# design.net
KiCad netlist of a schematic drawn in Altium Designer
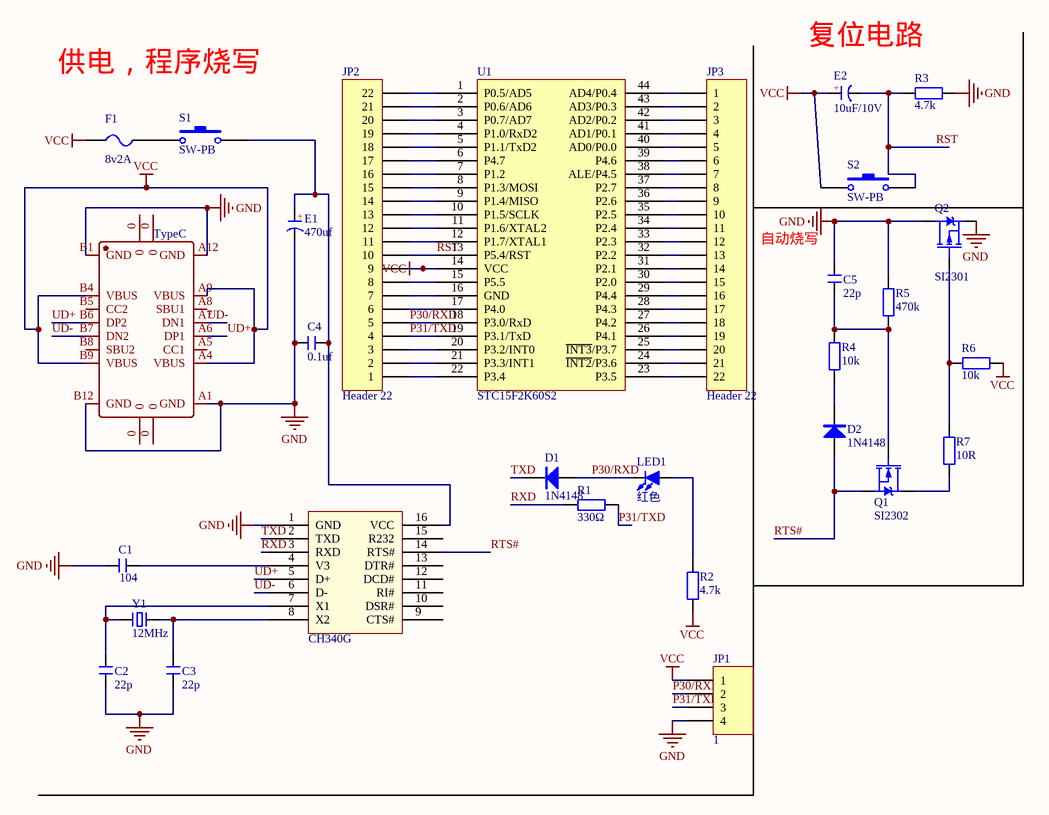
[diagram p0: 小车.SchDoc]

(export (version "E")
  (design (tool "Eeschema 10.0.6"))
  (components
    (comp (ref "C1")
      (value "104")
      (footprint "C 0805")
      (description "无极性贴片电容")
      (fields (field (name "版权归属") "黎明电子style"))
      (libsource (lib "基地硬件部AD库3.01") (part "C"))
    )
    (comp (ref "C2")
      (value "22p")
      (footprint "C 0805")
      (description "无极性贴片电容")
      (fields (field (name "版权归属") "黎明电子style"))
      (libsource (lib "基地硬件部AD库3.01") (part "C"))
    )
    (comp (ref "C3")
      (value "22p")
      (footprint "C 0805")
      (description "无极性贴片电容")
      (fields (field (name "版权归属") "黎明电子style"))
      (libsource (lib "基地硬件部AD库3.01") (part "C"))
    )
    (comp (ref "C4")
      (value "0.1uf")
      (footprint "C 0805")
      (description "无极性贴片电容")
      (fields (field (name "版权归属") "黎明电子style"))
      (libsource (lib "基地硬件部AD库3.01") (part "C"))
    )
    (comp (ref "C5")
      (value "22p")
      (footprint "C 0805")
      (description "无极性贴片电容")
      (fields (field (name "版权归属") "黎明电子style"))
      (libsource (lib "基地硬件部AD库3.01") (part "C"))
    )
    (comp (ref "CH340G") (value "CH340G") (footprint "sop16_L") (libsource (lib "主集成库") (part "CH340G")))
    (comp (ref "D1")
      (value "1N4148")
      (footprint "MINI_MELF (LL34)")
      (description "高速开关二极管")
      (fields (field (name "版权归属") "源创客"))
      (libsource (lib "基地硬件部AD库3.01") (part "1N4148"))
    )
    (comp (ref "D2")
      (value "1N4148")
      (footprint "MINI_MELF (LL34)")
      (description "高速开关二极管")
      (fields (field (name "版权归属") "源创客"))
      (libsource (lib "基地硬件部AD库3.01") (part "1N4148"))
    )
    (comp (ref "E1")
      (value "470uf")
      (footprint "CM A(3*5.4)")
      (description "贴片电解电容")
      (fields (field (name "版权归属") "黎明电子style"))
      (libsource (lib "") (part "C-CM_1"))
    )
    (comp (ref "E2")
      (value "10uF/10V")
      (footprint "CM A(3*5.4)")
      (description "贴片电解电容")
      (fields (field (name "版权归属") "黎明电子style"))
      (libsource (lib "基地硬件部AD库3.01") (part "C-CM"))
    )
    (comp (ref "F1")
      (value "8v2A")
      (footprint "FU 0402")
      (description "贴片保险丝")
      (fields (field (name "版权归属") "源创客"))
      (libsource (lib "基地硬件部AD库3.01") (part "FU"))
    )
    (comp (ref "JP1")
      (value "1")
      (footprint "HDR1X4")
      (description "Header, 4-Pin")
      (fields (field (name "PUBLISHER") "Altium Limited"))
      (libsource (lib "Miscellaneous Connectors") (part "Header 4"))
    )
    (comp (ref "JP2")
      (value "Header 22")
      (footprint "HDR1X22")
      (description "Header, 22-Pin")
      (fields (field (name "PUBLISHER") "Altium Limited"))
      (libsource (lib "Miscellaneous Connectors") (part "Header 22"))
    )
    (comp (ref "JP3")
      (value "Header 22")
      (footprint "HDR1X22")
      (description "Header, 22-Pin")
      (fields (field (name "PUBLISHER") "Altium Limited"))
      (libsource (lib "") (part "Header 22_1"))
    )
    (comp (ref "LED1")
      (value "红色")
      (footprint "LED 0805G")
      (description "贴片LED")
      (fields (field (name "版权归属") "黎明电子style"))
      (libsource (lib "基地硬件部AD库3.01") (part "LED-SMD"))
    )
    (comp (ref "Q1")
      (value "SI2302")
      (footprint "SOT23-3N")
      (description "N沟道场效应管")
      (fields (field (name "版权归属") "黎明电子style"))
      (libsource (lib "基地硬件部AD库3.01") (part "SI2302"))
    )
    (comp (ref "Q2")
      (value "SI2301")
      (footprint "SOT23-3N")
      (description "P沟道场效应管")
      (fields (field (name "版权归属") "黎明电子style"))
      (libsource (lib "基地硬件部AD库3.01") (part "SI2301"))
    )
    (comp (ref "R1")
      (value "330Ω")
      (footprint "R 0805")
      (description "贴片电阻")
      (fields (field (name "版权归属") "黎明电子style"))
      (libsource (lib "基地硬件部AD库3.01") (part "R"))
    )
    (comp (ref "R2")
      (value "4.7k")
      (footprint "R 0805")
      (description "贴片电阻")
      (fields (field (name "版权归属") "黎明电子style"))
      (libsource (lib "基地硬件部AD库3.01") (part "R"))
    )
    (comp (ref "R3")
      (value "4.7k")
      (footprint "R 0805")
      (description "贴片电阻")
      (fields (field (name "版权归属") "黎明电子style"))
      (libsource (lib "基地硬件部AD库3.01") (part "R"))
    )
    (comp (ref "R4")
      (value "10k")
      (footprint "R 0805")
      (description "贴片电阻")
      (fields (field (name "版权归属") "黎明电子style"))
      (libsource (lib "基地硬件部AD库3.01") (part "R"))
    )
    (comp (ref "R5")
      (value "470k")
      (footprint "R 0805")
      (description "贴片电阻")
      (fields (field (name "版权归属") "黎明电子style"))
      (libsource (lib "基地硬件部AD库3.01") (part "R"))
    )
    (comp (ref "R6")
      (value "10k")
      (footprint "R 0805")
      (description "贴片电阻")
      (fields (field (name "版权归属") "黎明电子style"))
      (libsource (lib "基地硬件部AD库3.01") (part "R"))
    )
    (comp (ref "R7")
      (value "10R")
      (footprint "R 0805")
      (description "贴片电阻")
      (fields (field (name "版权归属") "黎明电子style"))
      (libsource (lib "基地硬件部AD库3.01") (part "R"))
    )
    (comp (ref "S1")
      (value "SW-PB")
      (footprint "SW_PB2_A1")
      (description "微动开关")
      (fields (field (name "PUBLISHER") "Altium Limited"))
      (libsource (lib "主集成库") (part "SW-PB"))
    )
    (comp (ref "S2")
      (value "SW-PB")
      (footprint "SW_PB2_A1")
      (description "微动开关")
      (fields (field (name "PUBLISHER") "Altium Limited"))
      (libsource (lib "主集成库") (part "SW-PB"))
    )
    (comp (ref "TypeC")
      (value "TypeC-16pin")
      (footprint "typeC-16pin")
      (description "USB-C-16Pin")
      (libsource (lib "基地硬件部AD库3.01") (part "TypeC-16pin"))
    )
    (comp (ref "U1")
      (value "STC15F2K60S2")
      (footprint "LQFP44 10X10_L")
      (description "STC单片机")
      (fields (field (name "版权归属") "校基地硬件部"))
      (libsource (lib "基地硬件部AD库3.01") (part "STC15F2K60S2-44pin"))
    )
    (comp (ref "Y1")
      (value "12MHz")
      (footprint "OSC HC-49SMD")
      (description "2脚无源脚晶振")
      (fields (field (name "版权归属") "源创客"))
      (libsource (lib "基地硬件部AD库3.01") (part "XTAL-2P"))
    )
  )
  (nets
    (net (code "1") (name "/P30{slash}RXD") (class "Default")
      (node (ref "D1") (pin "1") (pinfunction "A_1") (pintype "passive"))
      (node (ref "JP1") (pin "2") (pinfunction "2_2") (pintype "passive"))
      (node (ref "JP2") (pin "5") (pinfunction "5_5") (pintype "passive"))
      (node (ref "LED1") (pin "2") (pinfunction "K_2") (pintype "passive"))
      (node (ref "U1") (pin "18") (pinfunction "P3.0/RxD_18") (pintype "passive"))
    )
    (net (code "2") (name "/P31{slash}TXD") (class "Default")
      (node (ref "JP1") (pin "3") (pinfunction "3_3") (pintype "passive"))
      (node (ref "JP2") (pin "4") (pinfunction "4_4") (pintype "passive"))
      (node (ref "R1") (pin "2") (pinfunction "2_2") (pintype "passive"))
      (node (ref "U1") (pin "19") (pinfunction "P3.1/TxD_19") (pintype "passive"))
    )
    (net (code "3") (name "/RST") (class "Default")
      (node (ref "E2") (pin "2") (pinfunction "K_2") (pintype "passive"))
      (node (ref "JP2") (pin "10") (pinfunction "10_10") (pintype "passive"))
      (node (ref "R3") (pin "2") (pinfunction "2_2") (pintype "passive"))
      (node (ref "S2") (pin "2") (pinfunction "2_2") (pintype "passive"))
      (node (ref "U1") (pin "13") (pinfunction "P5.4/RST_13") (pintype "passive"))
    )
    (net (code "4") (name "/RTS#") (class "Default")
      (node (ref "CH340G") (pin "14") (pinfunction "RTS#_14") (pintype "passive"))
      (node (ref "D2") (pin "1") (pinfunction "A_1") (pintype "passive"))
      (node (ref "Q1") (pin "2") (pinfunction "S_2") (pintype "passive"))
    )
    (net (code "5") (name "/RXD") (class "Default")
      (node (ref "CH340G") (pin "3") (pinfunction "RXD_3") (pintype "passive"))
      (node (ref "R1") (pin "1") (pinfunction "1_1") (pintype "passive"))
    )
    (net (code "6") (name "/TXD") (class "Default")
      (node (ref "CH340G") (pin "2") (pinfunction "TXD_2") (pintype "passive"))
      (node (ref "D1") (pin "2") (pinfunction "K_2") (pintype "passive"))
    )
    (net (code "7") (name "/UD+") (class "Default")
      (node (ref "CH340G") (pin "5") (pinfunction "D+_5") (pintype "passive"))
      (node (ref "TypeC") (pin "A6") (pinfunction "DP1_A6") (pintype "passive"))
      (node (ref "TypeC") (pin "B6") (pinfunction "DP2_B6") (pintype "passive"))
    )
    (net (code "8") (name "/UD-") (class "Default")
      (node (ref "CH340G") (pin "6") (pinfunction "D-_6") (pintype "passive"))
      (node (ref "TypeC") (pin "A7") (pinfunction "DN1_A7") (pintype "passive"))
      (node (ref "TypeC") (pin "B7") (pinfunction "DN2_B7") (pintype "passive"))
    )
    (net (code "9") (name "GND") (class "Default")
      (node (ref "C1") (pin "1") (pinfunction "1_1") (pintype "passive"))
      (node (ref "C2") (pin "2") (pinfunction "2_2") (pintype "passive"))
      (node (ref "C3") (pin "2") (pinfunction "2_2") (pintype "passive"))
      (node (ref "C4") (pin "1") (pinfunction "1_1") (pintype "passive"))
      (node (ref "C5") (pin "1") (pinfunction "1_1") (pintype "passive"))
      (node (ref "CH340G") (pin "1") (pinfunction "GND_1") (pintype "passive"))
      (node (ref "E1") (pin "2") (pinfunction "K_2") (pintype "passive"))
      (node (ref "JP1") (pin "4") (pinfunction "4_4") (pintype "passive"))
      (node (ref "Q2") (pin "2") (pinfunction "S_2") (pintype "passive"))
      (node (ref "Q2") (pin "3") (pinfunction "D_3") (pintype "passive"))
      (node (ref "R3") (pin "1") (pinfunction "1_1") (pintype "passive"))
      (node (ref "R5") (pin "1") (pinfunction "1_1") (pintype "passive"))
      (node (ref "TypeC") (pin "A1") (pinfunction "GND_A1") (pintype "passive"))
      (node (ref "TypeC") (pin "A12") (pinfunction "GND_A12") (pintype "passive"))
      (node (ref "TypeC") (pin "B1") (pinfunction "GND_B1") (pintype "passive"))
      (node (ref "TypeC") (pin "B12") (pinfunction "GND_B12") (pintype "passive"))
    )
    (net (code "10") (name "Net-(CH340G-V3)") (class "Default")
      (node (ref "C1") (pin "2") (pinfunction "2_2") (pintype "passive"))
      (node (ref "CH340G") (pin "4") (pinfunction "V3_4") (pintype "passive"))
    )
    (net (code "11") (name "Net-(CH340G-VCC)") (class "Default")
      (node (ref "C4") (pin "2") (pinfunction "2_2") (pintype "passive"))
      (node (ref "CH340G") (pin "16") (pinfunction "VCC_16") (pintype "passive"))
      (node (ref "E1") (pin "1") (pinfunction "A_1") (pintype "passive"))
      (node (ref "S1") (pin "2") (pinfunction "2_2") (pintype "passive"))
    )
    (net (code "12") (name "Net-(CH340G-X1)") (class "Default")
      (node (ref "C2") (pin "1") (pinfunction "1_1") (pintype "passive"))
      (node (ref "CH340G") (pin "7") (pinfunction "X1_7") (pintype "passive"))
      (node (ref "Y1") (pin "1") (pinfunction "1_1") (pintype "passive"))
    )
    (net (code "13") (name "Net-(CH340G-X2)") (class "Default")
      (node (ref "C3") (pin "1") (pinfunction "1_1") (pintype "passive"))
      (node (ref "CH340G") (pin "8") (pinfunction "X2_8") (pintype "passive"))
      (node (ref "Y1") (pin "2") (pinfunction "2_2") (pintype "passive"))
    )
    (net (code "14") (name "Net-(D2-K)") (class "Default")
      (node (ref "D2") (pin "2") (pinfunction "K_2") (pintype "passive"))
      (node (ref "R4") (pin "2") (pinfunction "2_2") (pintype "passive"))
    )
    (net (code "15") (name "Net-(F1-Pad2)") (class "Default")
      (node (ref "F1") (pin "2") (pinfunction "2_2") (pintype "passive"))
      (node (ref "S1") (pin "1") (pinfunction "1_1") (pintype "passive"))
    )
    (net (code "16") (name "Net-(LED1-A)") (class "Default")
      (node (ref "LED1") (pin "1") (pinfunction "A_1") (pintype "passive"))
      (node (ref "R2") (pin "1") (pinfunction "1_1") (pintype "passive"))
    )
    (net (code "17") (name "Net-(Q1-D)") (class "Default")
      (node (ref "Q1") (pin "3") (pinfunction "D_3") (pintype "passive"))
      (node (ref "R7") (pin "2") (pinfunction "2_2") (pintype "passive"))
    )
    (net (code "18") (name "Net-(Q1-G)") (class "Default")
      (node (ref "C5") (pin "2") (pinfunction "2_2") (pintype "passive"))
      (node (ref "Q1") (pin "1") (pinfunction "G_1") (pintype "passive"))
      (node (ref "R4") (pin "1") (pinfunction "1_1") (pintype "passive"))
      (node (ref "R5") (pin "2") (pinfunction "2_2") (pintype "passive"))
    )
    (net (code "19") (name "Net-(Q2-G)") (class "Default")
      (node (ref "Q2") (pin "1") (pinfunction "G_1") (pintype "passive"))
      (node (ref "R6") (pin "2") (pinfunction "2_2") (pintype "passive"))
      (node (ref "R7") (pin "1") (pinfunction "1_1") (pintype "passive"))
    )
    (net (code "20") (name "Net-(U1-AD0{slash}P0.0)") (class "Default")
      (node (ref "JP3") (pin "5") (pinfunction "5_5") (pintype "passive"))
      (node (ref "U1") (pin "40") (pinfunction "AD0/P0.0_40") (pintype "passive"))
    )
    (net (code "21") (name "Net-(U1-AD1{slash}P0.1)") (class "Default")
      (node (ref "JP3") (pin "4") (pinfunction "4_4") (pintype "passive"))
      (node (ref "U1") (pin "41") (pinfunction "AD1/P0.1_41") (pintype "passive"))
    )
    (net (code "22") (name "Net-(U1-AD2{slash}P0.2)") (class "Default")
      (node (ref "JP3") (pin "3") (pinfunction "3_3") (pintype "passive"))
      (node (ref "U1") (pin "42") (pinfunction "AD2/P0.2_42") (pintype "passive"))
    )
    (net (code "23") (name "Net-(U1-AD3{slash}P0.3)") (class "Default")
      (node (ref "JP3") (pin "2") (pinfunction "2_2") (pintype "passive"))
      (node (ref "U1") (pin "43") (pinfunction "AD3/P0.3_43") (pintype "passive"))
    )
    (net (code "24") (name "Net-(U1-AD4{slash}P0.4)") (class "Default")
      (node (ref "JP3") (pin "1") (pinfunction "1_1") (pintype "passive"))
      (node (ref "U1") (pin "44") (pinfunction "AD4/P0.4_44") (pintype "passive"))
    )
    (net (code "25") (name "Net-(U1-ALE{slash}P4.5)") (class "Default")
      (node (ref "JP3") (pin "7") (pinfunction "7_7") (pintype "passive"))
      (node (ref "U1") (pin "38") (pinfunction "ALE/P4.5_38") (pintype "passive"))
    )
    (net (code "26") (name "Net-(U1-GND)") (class "Default")
      (node (ref "JP2") (pin "7") (pinfunction "7_7") (pintype "passive"))
      (node (ref "U1") (pin "16") (pinfunction "GND_16") (pintype "passive"))
    )
    (net (code "27") (name "Net-(U1-P0.5{slash}AD5)") (class "Default")
      (node (ref "JP2") (pin "22") (pinfunction "22_22") (pintype "passive"))
      (node (ref "U1") (pin "1") (pinfunction "P0.5/AD5_1") (pintype "passive"))
    )
    (net (code "28") (name "Net-(U1-P0.6{slash}AD6)") (class "Default")
      (node (ref "JP2") (pin "21") (pinfunction "21_21") (pintype "passive"))
      (node (ref "U1") (pin "2") (pinfunction "P0.6/AD6_2") (pintype "passive"))
    )
    (net (code "29") (name "Net-(U1-P0.7{slash}AD7)") (class "Default")
      (node (ref "JP2") (pin "20") (pinfunction "20_20") (pintype "passive"))
      (node (ref "U1") (pin "3") (pinfunction "P0.7/AD7_3") (pintype "passive"))
    )
    (net (code "30") (name "Net-(U1-P1.0{slash}RxD2)") (class "Default")
      (node (ref "JP2") (pin "19") (pinfunction "19_19") (pintype "passive"))
      (node (ref "U1") (pin "4") (pinfunction "P1.0/RxD2_4") (pintype "passive"))
    )
    (net (code "31") (name "Net-(U1-P1.1{slash}TxD2)") (class "Default")
      (node (ref "JP2") (pin "18") (pinfunction "18_18") (pintype "passive"))
      (node (ref "U1") (pin "5") (pinfunction "P1.1/TxD2_5") (pintype "passive"))
    )
    (net (code "32") (name "Net-(U1-P1.2)") (class "Default")
      (node (ref "JP2") (pin "16") (pinfunction "16_16") (pintype "passive"))
      (node (ref "U1") (pin "7") (pinfunction "P1.2_7") (pintype "passive"))
    )
    (net (code "33") (name "Net-(U1-P1.3{slash}MOSI)") (class "Default")
      (node (ref "JP2") (pin "15") (pinfunction "15_15") (pintype "passive"))
      (node (ref "U1") (pin "8") (pinfunction "P1.3/MOSI_8") (pintype "passive"))
    )
    (net (code "34") (name "Net-(U1-P1.4{slash}MISO)") (class "Default")
      (node (ref "JP2") (pin "14") (pinfunction "14_14") (pintype "passive"))
      (node (ref "U1") (pin "9") (pinfunction "P1.4/MISO_9") (pintype "passive"))
    )
    (net (code "35") (name "Net-(U1-P1.5{slash}SCLK)") (class "Default")
      (node (ref "JP2") (pin "13") (pinfunction "13_13") (pintype "passive"))
      (node (ref "U1") (pin "10") (pinfunction "P1.5/SCLK_10") (pintype "passive"))
    )
    (net (code "36") (name "Net-(U1-P1.6{slash}XTAL2)") (class "Default")
      (node (ref "JP2") (pin "12") (pinfunction "12_12") (pintype "passive"))
      (node (ref "U1") (pin "11") (pinfunction "P1.6/XTAL2_11") (pintype "passive"))
    )
    (net (code "37") (name "Net-(U1-P1.7{slash}XTAL1)") (class "Default")
      (node (ref "JP2") (pin "11") (pinfunction "11_11") (pintype "passive"))
      (node (ref "U1") (pin "12") (pinfunction "P1.7/XTAL1_12") (pintype "passive"))
    )
    (net (code "38") (name "Net-(U1-P2.0)") (class "Default")
      (node (ref "JP3") (pin "15") (pinfunction "15_15") (pintype "passive"))
      (node (ref "U1") (pin "30") (pinfunction "P2.0_30") (pintype "passive"))
    )
    (net (code "39") (name "Net-(U1-P2.1)") (class "Default")
      (node (ref "JP3") (pin "14") (pinfunction "14_14") (pintype "passive"))
      (node (ref "U1") (pin "31") (pinfunction "P2.1_31") (pintype "passive"))
    )
    (net (code "40") (name "Net-(U1-P2.2)") (class "Default")
      (node (ref "JP3") (pin "13") (pinfunction "13_13") (pintype "passive"))
      (node (ref "U1") (pin "32") (pinfunction "P2.2_32") (pintype "passive"))
    )
    (net (code "41") (name "Net-(U1-P2.3)") (class "Default")
      (node (ref "JP3") (pin "12") (pinfunction "12_12") (pintype "passive"))
      (node (ref "U1") (pin "33") (pinfunction "P2.3_33") (pintype "passive"))
    )
    (net (code "42") (name "Net-(U1-P2.4)") (class "Default")
      (node (ref "JP3") (pin "11") (pinfunction "11_11") (pintype "passive"))
      (node (ref "U1") (pin "34") (pinfunction "P2.4_34") (pintype "passive"))
    )
    (net (code "43") (name "Net-(U1-P2.5)") (class "Default")
      (node (ref "JP3") (pin "10") (pinfunction "10_10") (pintype "passive"))
      (node (ref "U1") (pin "35") (pinfunction "P2.5_35") (pintype "passive"))
    )
    (net (code "44") (name "Net-(U1-P2.6)") (class "Default")
      (node (ref "JP3") (pin "9") (pinfunction "9_9") (pintype "passive"))
      (node (ref "U1") (pin "36") (pinfunction "P2.6_36") (pintype "passive"))
    )
    (net (code "45") (name "Net-(U1-P2.7)") (class "Default")
      (node (ref "JP3") (pin "8") (pinfunction "8_8") (pintype "passive"))
      (node (ref "U1") (pin "37") (pinfunction "P2.7_37") (pintype "passive"))
    )
    (net (code "46") (name "Net-(U1-P3.2{slash}INT0)") (class "Default")
      (node (ref "JP2") (pin "3") (pinfunction "3_3") (pintype "passive"))
      (node (ref "U1") (pin "20") (pinfunction "P3.2/INT0_20") (pintype "passive"))
    )
    (net (code "47") (name "Net-(U1-P3.3{slash}INT1)") (class "Default")
      (node (ref "JP2") (pin "2") (pinfunction "2_2") (pintype "passive"))
      (node (ref "U1") (pin "21") (pinfunction "P3.3/INT1_21") (pintype "passive"))
    )
    (net (code "48") (name "Net-(U1-P3.4)") (class "Default")
      (node (ref "JP2") (pin "1") (pinfunction "1_1") (pintype "passive"))
      (node (ref "U1") (pin "22") (pinfunction "P3.4_22") (pintype "passive"))
    )
    (net (code "49") (name "Net-(U1-P3.5)") (class "Default")
      (node (ref "JP3") (pin "22") (pinfunction "22_22") (pintype "passive"))
      (node (ref "U1") (pin "23") (pinfunction "P3.5_23") (pintype "passive"))
    )
    (net (code "50") (name "Net-(U1-P4.0)") (class "Default")
      (node (ref "JP2") (pin "6") (pinfunction "6_6") (pintype "passive"))
      (node (ref "U1") (pin "17") (pinfunction "P4.0_17") (pintype "passive"))
    )
    (net (code "51") (name "Net-(U1-P4.1)") (class "Default")
      (node (ref "JP3") (pin "19") (pinfunction "19_19") (pintype "passive"))
      (node (ref "U1") (pin "26") (pinfunction "P4.1_26") (pintype "passive"))
    )
    (net (code "52") (name "Net-(U1-P4.2)") (class "Default")
      (node (ref "JP3") (pin "18") (pinfunction "18_18") (pintype "passive"))
      (node (ref "U1") (pin "27") (pinfunction "P4.2_27") (pintype "passive"))
    )
    (net (code "53") (name "Net-(U1-P4.3)") (class "Default")
      (node (ref "JP3") (pin "17") (pinfunction "17_17") (pintype "passive"))
      (node (ref "U1") (pin "28") (pinfunction "P4.3_28") (pintype "passive"))
    )
    (net (code "54") (name "Net-(U1-P4.4)") (class "Default")
      (node (ref "JP3") (pin "16") (pinfunction "16_16") (pintype "passive"))
      (node (ref "U1") (pin "29") (pinfunction "P4.4_29") (pintype "passive"))
    )
    (net (code "55") (name "Net-(U1-P4.6)") (class "Default")
      (node (ref "JP3") (pin "6") (pinfunction "6_6") (pintype "passive"))
      (node (ref "U1") (pin "39") (pinfunction "P4.6_39") (pintype "passive"))
    )
    (net (code "56") (name "Net-(U1-P4.7)") (class "Default")
      (node (ref "JP2") (pin "17") (pinfunction "17_17") (pintype "passive"))
      (node (ref "U1") (pin "6") (pinfunction "P4.7_6") (pintype "passive"))
    )
    (net (code "57") (name "Net-(U1-P5.5)") (class "Default")
      (node (ref "JP2") (pin "8") (pinfunction "8_8") (pintype "passive"))
      (node (ref "U1") (pin "15") (pinfunction "P5.5_15") (pintype "passive"))
    )
    (net (code "58") (name "Net-(U1-~{INT2}{slash}P3.6)") (class "Default")
      (node (ref "JP3") (pin "21") (pinfunction "21_21") (pintype "passive"))
      (node (ref "U1") (pin "24") (pinfunction "~{INT2}/P3.6_24") (pintype "passive"))
    )
    (net (code "59") (name "Net-(U1-~{INT3}{slash}P3.7)") (class "Default")
      (node (ref "JP3") (pin "20") (pinfunction "20_20") (pintype "passive"))
      (node (ref "U1") (pin "25") (pinfunction "~{INT3}/P3.7_25") (pintype "passive"))
    )
    (net (code "60") (name "VCC") (class "Default")
      (node (ref "E2") (pin "1") (pinfunction "A_1") (pintype "passive"))
      (node (ref "F1") (pin "1") (pinfunction "1_1") (pintype "passive"))
      (node (ref "JP1") (pin "1") (pinfunction "1_1") (pintype "passive"))
      (node (ref "JP2") (pin "9") (pinfunction "9_9") (pintype "passive"))
      (node (ref "R2") (pin "2") (pinfunction "2_2") (pintype "passive"))
      (node (ref "R6") (pin "1") (pinfunction "1_1") (pintype "passive"))
      (node (ref "S2") (pin "1") (pinfunction "1_1") (pintype "passive"))
      (node (ref "TypeC") (pin "A4") (pinfunction "VBUS_A4") (pintype "passive"))
      (node (ref "TypeC") (pin "A9") (pinfunction "VBUS_A9") (pintype "passive"))
      (node (ref "TypeC") (pin "B4") (pinfunction "VBUS_B4") (pintype "passive"))
      (node (ref "TypeC") (pin "B9") (pinfunction "VBUS_B9") (pintype "passive"))
      (node (ref "U1") (pin "14") (pinfunction "VCC_14") (pintype "passive"))
    )
    (net (code "61") (name "unconnected-(CH340G-CTS#-Pad9)") (class "Default")
      (node (ref "CH340G") (pin "9") (pinfunction "CTS#_9") (pintype "passive"))
    )
    (net (code "62") (name "unconnected-(CH340G-DCD#-Pad12)") (class "Default")
      (node (ref "CH340G") (pin "12") (pinfunction "DCD#_12") (pintype "passive"))
    )
    (net (code "63") (name "unconnected-(CH340G-DSR#-Pad10)") (class "Default")
      (node (ref "CH340G") (pin "10") (pinfunction "DSR#_10") (pintype "passive"))
    )
    (net (code "64") (name "unconnected-(CH340G-DTR#-Pad13)") (class "Default")
      (node (ref "CH340G") (pin "13") (pinfunction "DTR#_13") (pintype "passive"))
    )
    (net (code "65") (name "unconnected-(CH340G-R232-Pad15)") (class "Default")
      (node (ref "CH340G") (pin "15") (pinfunction "R232_15") (pintype "passive"))
    )
    (net (code "66") (name "unconnected-(CH340G-RI#-Pad11)") (class "Default")
      (node (ref "CH340G") (pin "11") (pinfunction "RI#_11") (pintype "passive"))
    )
    (net (code "67") (name "unconnected-(TypeC-CC1-PadA5)") (class "Default")
      (node (ref "TypeC") (pin "A5") (pinfunction "CC1_A5") (pintype "passive"))
    )
    (net (code "68") (name "unconnected-(TypeC-CC2-PadB5)") (class "Default")
      (node (ref "TypeC") (pin "B5") (pinfunction "CC2_B5") (pintype "passive"))
    )
    (net (code "69") (name "unconnected-(TypeC-Pad0)") (class "Default")
      (node (ref "TypeC") (pin "0") (pinfunction "0_0") (pintype "passive"))
    )
    (net (code "70") (name "unconnected-(TypeC-Pad0)_1") (class "Default")
      (node (ref "TypeC") (pin "0") (pinfunction "0_0") (pintype "passive"))
    )
    (net (code "71") (name "unconnected-(TypeC-Pad0)_2") (class "Default")
      (node (ref "TypeC") (pin "0") (pinfunction "0_0") (pintype "passive"))
    )
    (net (code "72") (name "unconnected-(TypeC-Pad0)_3") (class "Default")
      (node (ref "TypeC") (pin "0") (pinfunction "0_0") (pintype "passive"))
    )
    (net (code "73") (name "unconnected-(TypeC-SBU1-PadA8)") (class "Default")
      (node (ref "TypeC") (pin "A8") (pinfunction "SBU1_A8") (pintype "passive"))
    )
    (net (code "74") (name "unconnected-(TypeC-SBU2-PadB8)") (class "Default")
      (node (ref "TypeC") (pin "B8") (pinfunction "SBU2_B8") (pintype "passive"))
    )
  )
)
